# SubBus8.net
KiCad netlist of a schematic drawn in Altium Designer
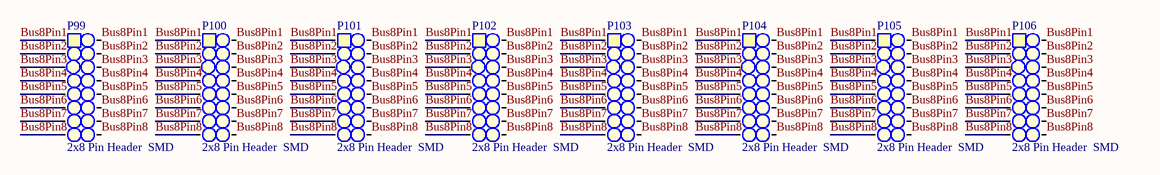
[diagram p0: SubBus8.SchDoc]

(export (version "E")
  (design (tool "Eeschema 10.0.6"))
  (components
    (comp (ref "P99")
      (value "2x8 Pin Header  SMD")
      (footprint "2X8_SMD_PH_2.54")
      (description "2.54mm, SMD")
      (libsource (lib "jclib") (part "2x8 Pin Header  SMD"))
    )
    (comp (ref "P100")
      (value "2x8 Pin Header  SMD")
      (footprint "2X8_SMD_PH_2.54")
      (description "2.54mm, SMD")
      (libsource (lib "jclib") (part "2x8 Pin Header  SMD"))
    )
    (comp (ref "P101")
      (value "2x8 Pin Header  SMD")
      (footprint "2X8_SMD_PH_2.54")
      (description "2.54mm, SMD")
      (libsource (lib "jclib") (part "2x8 Pin Header  SMD"))
    )
    (comp (ref "P102")
      (value "2x8 Pin Header  SMD")
      (footprint "2X8_SMD_PH_2.54")
      (description "2.54mm, SMD")
      (libsource (lib "jclib") (part "2x8 Pin Header  SMD"))
    )
    (comp (ref "P103")
      (value "2x8 Pin Header  SMD")
      (footprint "2X8_SMD_PH_2.54")
      (description "2.54mm, SMD")
      (libsource (lib "jclib") (part "2x8 Pin Header  SMD"))
    )
    (comp (ref "P104")
      (value "2x8 Pin Header  SMD")
      (footprint "2X8_SMD_PH_2.54")
      (description "2.54mm, SMD")
      (libsource (lib "jclib") (part "2x8 Pin Header  SMD"))
    )
    (comp (ref "P105")
      (value "2x8 Pin Header  SMD")
      (footprint "2X8_SMD_PH_2.54")
      (description "2.54mm, SMD")
      (libsource (lib "jclib") (part "2x8 Pin Header  SMD"))
    )
    (comp (ref "P106")
      (value "2x8 Pin Header  SMD")
      (footprint "2X8_SMD_PH_2.54")
      (description "2.54mm, SMD")
      (libsource (lib "jclib") (part "2x8 Pin Header  SMD"))
    )
  )
  (nets
    (net (code "1") (name "/Bus8Pin1") (class "Default")
      (node (ref "P100") (pin "1") (pinfunction "1_1") (pintype "passive"))
      (node (ref "P100") (pin "16") (pinfunction "16_16") (pintype "passive"))
      (node (ref "P101") (pin "1") (pinfunction "1_1") (pintype "passive"))
      (node (ref "P101") (pin "16") (pinfunction "16_16") (pintype "passive"))
      (node (ref "P102") (pin "1") (pinfunction "1_1") (pintype "passive"))
      (node (ref "P102") (pin "16") (pinfunction "16_16") (pintype "passive"))
      (node (ref "P103") (pin "1") (pinfunction "1_1") (pintype "passive"))
      (node (ref "P103") (pin "16") (pinfunction "16_16") (pintype "passive"))
      (node (ref "P104") (pin "1") (pinfunction "1_1") (pintype "passive"))
      (node (ref "P104") (pin "16") (pinfunction "16_16") (pintype "passive"))
      (node (ref "P105") (pin "1") (pinfunction "1_1") (pintype "passive"))
      (node (ref "P105") (pin "16") (pinfunction "16_16") (pintype "passive"))
      (node (ref "P106") (pin "1") (pinfunction "1_1") (pintype "passive"))
      (node (ref "P106") (pin "16") (pinfunction "16_16") (pintype "passive"))
      (node (ref "P99") (pin "1") (pinfunction "1_1") (pintype "passive"))
      (node (ref "P99") (pin "16") (pinfunction "16_16") (pintype "passive"))
    )
    (net (code "2") (name "/Bus8Pin2") (class "Default")
      (node (ref "P100") (pin "15") (pinfunction "15_15") (pintype "passive"))
      (node (ref "P100") (pin "2") (pinfunction "2_2") (pintype "passive"))
      (node (ref "P101") (pin "15") (pinfunction "15_15") (pintype "passive"))
      (node (ref "P101") (pin "2") (pinfunction "2_2") (pintype "passive"))
      (node (ref "P102") (pin "15") (pinfunction "15_15") (pintype "passive"))
      (node (ref "P102") (pin "2") (pinfunction "2_2") (pintype "passive"))
      (node (ref "P103") (pin "15") (pinfunction "15_15") (pintype "passive"))
      (node (ref "P103") (pin "2") (pinfunction "2_2") (pintype "passive"))
      (node (ref "P104") (pin "15") (pinfunction "15_15") (pintype "passive"))
      (node (ref "P104") (pin "2") (pinfunction "2_2") (pintype "passive"))
      (node (ref "P105") (pin "15") (pinfunction "15_15") (pintype "passive"))
      (node (ref "P105") (pin "2") (pinfunction "2_2") (pintype "passive"))
      (node (ref "P106") (pin "15") (pinfunction "15_15") (pintype "passive"))
      (node (ref "P106") (pin "2") (pinfunction "2_2") (pintype "passive"))
      (node (ref "P99") (pin "15") (pinfunction "15_15") (pintype "passive"))
      (node (ref "P99") (pin "2") (pinfunction "2_2") (pintype "passive"))
    )
    (net (code "3") (name "/Bus8Pin3") (class "Default")
      (node (ref "P100") (pin "14") (pinfunction "14_14") (pintype "passive"))
      (node (ref "P100") (pin "3") (pinfunction "3_3") (pintype "passive"))
      (node (ref "P101") (pin "14") (pinfunction "14_14") (pintype "passive"))
      (node (ref "P101") (pin "3") (pinfunction "3_3") (pintype "passive"))
      (node (ref "P102") (pin "14") (pinfunction "14_14") (pintype "passive"))
      (node (ref "P102") (pin "3") (pinfunction "3_3") (pintype "passive"))
      (node (ref "P103") (pin "14") (pinfunction "14_14") (pintype "passive"))
      (node (ref "P103") (pin "3") (pinfunction "3_3") (pintype "passive"))
      (node (ref "P104") (pin "14") (pinfunction "14_14") (pintype "passive"))
      (node (ref "P104") (pin "3") (pinfunction "3_3") (pintype "passive"))
      (node (ref "P105") (pin "14") (pinfunction "14_14") (pintype "passive"))
      (node (ref "P105") (pin "3") (pinfunction "3_3") (pintype "passive"))
      (node (ref "P106") (pin "14") (pinfunction "14_14") (pintype "passive"))
      (node (ref "P106") (pin "3") (pinfunction "3_3") (pintype "passive"))
      (node (ref "P99") (pin "14") (pinfunction "14_14") (pintype "passive"))
      (node (ref "P99") (pin "3") (pinfunction "3_3") (pintype "passive"))
    )
    (net (code "4") (name "/Bus8Pin4") (class "Default")
      (node (ref "P100") (pin "13") (pinfunction "13_13") (pintype "passive"))
      (node (ref "P100") (pin "4") (pinfunction "4_4") (pintype "passive"))
      (node (ref "P101") (pin "13") (pinfunction "13_13") (pintype "passive"))
      (node (ref "P101") (pin "4") (pinfunction "4_4") (pintype "passive"))
      (node (ref "P102") (pin "13") (pinfunction "13_13") (pintype "passive"))
      (node (ref "P102") (pin "4") (pinfunction "4_4") (pintype "passive"))
      (node (ref "P103") (pin "13") (pinfunction "13_13") (pintype "passive"))
      (node (ref "P103") (pin "4") (pinfunction "4_4") (pintype "passive"))
      (node (ref "P104") (pin "13") (pinfunction "13_13") (pintype "passive"))
      (node (ref "P104") (pin "4") (pinfunction "4_4") (pintype "passive"))
      (node (ref "P105") (pin "13") (pinfunction "13_13") (pintype "passive"))
      (node (ref "P105") (pin "4") (pinfunction "4_4") (pintype "passive"))
      (node (ref "P106") (pin "13") (pinfunction "13_13") (pintype "passive"))
      (node (ref "P106") (pin "4") (pinfunction "4_4") (pintype "passive"))
      (node (ref "P99") (pin "13") (pinfunction "13_13") (pintype "passive"))
      (node (ref "P99") (pin "4") (pinfunction "4_4") (pintype "passive"))
    )
    (net (code "5") (name "/Bus8Pin5") (class "Default")
      (node (ref "P100") (pin "12") (pinfunction "12_12") (pintype "passive"))
      (node (ref "P100") (pin "5") (pinfunction "5_5") (pintype "passive"))
      (node (ref "P101") (pin "12") (pinfunction "12_12") (pintype "passive"))
      (node (ref "P101") (pin "5") (pinfunction "5_5") (pintype "passive"))
      (node (ref "P102") (pin "12") (pinfunction "12_12") (pintype "passive"))
      (node (ref "P102") (pin "5") (pinfunction "5_5") (pintype "passive"))
      (node (ref "P103") (pin "12") (pinfunction "12_12") (pintype "passive"))
      (node (ref "P103") (pin "5") (pinfunction "5_5") (pintype "passive"))
      (node (ref "P104") (pin "12") (pinfunction "12_12") (pintype "passive"))
      (node (ref "P104") (pin "5") (pinfunction "5_5") (pintype "passive"))
      (node (ref "P105") (pin "12") (pinfunction "12_12") (pintype "passive"))
      (node (ref "P105") (pin "5") (pinfunction "5_5") (pintype "passive"))
      (node (ref "P106") (pin "12") (pinfunction "12_12") (pintype "passive"))
      (node (ref "P106") (pin "5") (pinfunction "5_5") (pintype "passive"))
      (node (ref "P99") (pin "12") (pinfunction "12_12") (pintype "passive"))
      (node (ref "P99") (pin "5") (pinfunction "5_5") (pintype "passive"))
    )
    (net (code "6") (name "/Bus8Pin6") (class "Default")
      (node (ref "P100") (pin "11") (pinfunction "11_11") (pintype "passive"))
      (node (ref "P100") (pin "6") (pinfunction "6_6") (pintype "passive"))
      (node (ref "P101") (pin "11") (pinfunction "11_11") (pintype "passive"))
      (node (ref "P101") (pin "6") (pinfunction "6_6") (pintype "passive"))
      (node (ref "P102") (pin "11") (pinfunction "11_11") (pintype "passive"))
      (node (ref "P102") (pin "6") (pinfunction "6_6") (pintype "passive"))
      (node (ref "P103") (pin "11") (pinfunction "11_11") (pintype "passive"))
      (node (ref "P103") (pin "6") (pinfunction "6_6") (pintype "passive"))
      (node (ref "P104") (pin "11") (pinfunction "11_11") (pintype "passive"))
      (node (ref "P104") (pin "6") (pinfunction "6_6") (pintype "passive"))
      (node (ref "P105") (pin "11") (pinfunction "11_11") (pintype "passive"))
      (node (ref "P105") (pin "6") (pinfunction "6_6") (pintype "passive"))
      (node (ref "P106") (pin "11") (pinfunction "11_11") (pintype "passive"))
      (node (ref "P106") (pin "6") (pinfunction "6_6") (pintype "passive"))
      (node (ref "P99") (pin "11") (pinfunction "11_11") (pintype "passive"))
      (node (ref "P99") (pin "6") (pinfunction "6_6") (pintype "passive"))
    )
    (net (code "7") (name "/Bus8Pin7") (class "Default")
      (node (ref "P100") (pin "10") (pinfunction "10_10") (pintype "passive"))
      (node (ref "P100") (pin "7") (pinfunction "7_7") (pintype "passive"))
      (node (ref "P101") (pin "10") (pinfunction "10_10") (pintype "passive"))
      (node (ref "P101") (pin "7") (pinfunction "7_7") (pintype "passive"))
      (node (ref "P102") (pin "10") (pinfunction "10_10") (pintype "passive"))
      (node (ref "P102") (pin "7") (pinfunction "7_7") (pintype "passive"))
      (node (ref "P103") (pin "10") (pinfunction "10_10") (pintype "passive"))
      (node (ref "P103") (pin "7") (pinfunction "7_7") (pintype "passive"))
      (node (ref "P104") (pin "10") (pinfunction "10_10") (pintype "passive"))
      (node (ref "P104") (pin "7") (pinfunction "7_7") (pintype "passive"))
      (node (ref "P105") (pin "10") (pinfunction "10_10") (pintype "passive"))
      (node (ref "P105") (pin "7") (pinfunction "7_7") (pintype "passive"))
      (node (ref "P106") (pin "10") (pinfunction "10_10") (pintype "passive"))
      (node (ref "P106") (pin "7") (pinfunction "7_7") (pintype "passive"))
      (node (ref "P99") (pin "10") (pinfunction "10_10") (pintype "passive"))
      (node (ref "P99") (pin "7") (pinfunction "7_7") (pintype "passive"))
    )
    (net (code "8") (name "/Bus8Pin8") (class "Default")
      (node (ref "P100") (pin "8") (pinfunction "8_8") (pintype "passive"))
      (node (ref "P100") (pin "9") (pinfunction "9_9") (pintype "passive"))
      (node (ref "P101") (pin "8") (pinfunction "8_8") (pintype "passive"))
      (node (ref "P101") (pin "9") (pinfunction "9_9") (pintype "passive"))
      (node (ref "P102") (pin "8") (pinfunction "8_8") (pintype "passive"))
      (node (ref "P102") (pin "9") (pinfunction "9_9") (pintype "passive"))
      (node (ref "P103") (pin "8") (pinfunction "8_8") (pintype "passive"))
      (node (ref "P103") (pin "9") (pinfunction "9_9") (pintype "passive"))
      (node (ref "P104") (pin "8") (pinfunction "8_8") (pintype "passive"))
      (node (ref "P104") (pin "9") (pinfunction "9_9") (pintype "passive"))
      (node (ref "P105") (pin "8") (pinfunction "8_8") (pintype "passive"))
      (node (ref "P105") (pin "9") (pinfunction "9_9") (pintype "passive"))
      (node (ref "P106") (pin "8") (pinfunction "8_8") (pintype "passive"))
      (node (ref "P106") (pin "9") (pinfunction "9_9") (pintype "passive"))
      (node (ref "P99") (pin "8") (pinfunction "8_8") (pintype "passive"))
      (node (ref "P99") (pin "9") (pinfunction "9_9") (pintype "passive"))
    )
  )
)
